# RfM_v4_KOVAN.net
KiCad netlist of a schematic drawn in EAGLE
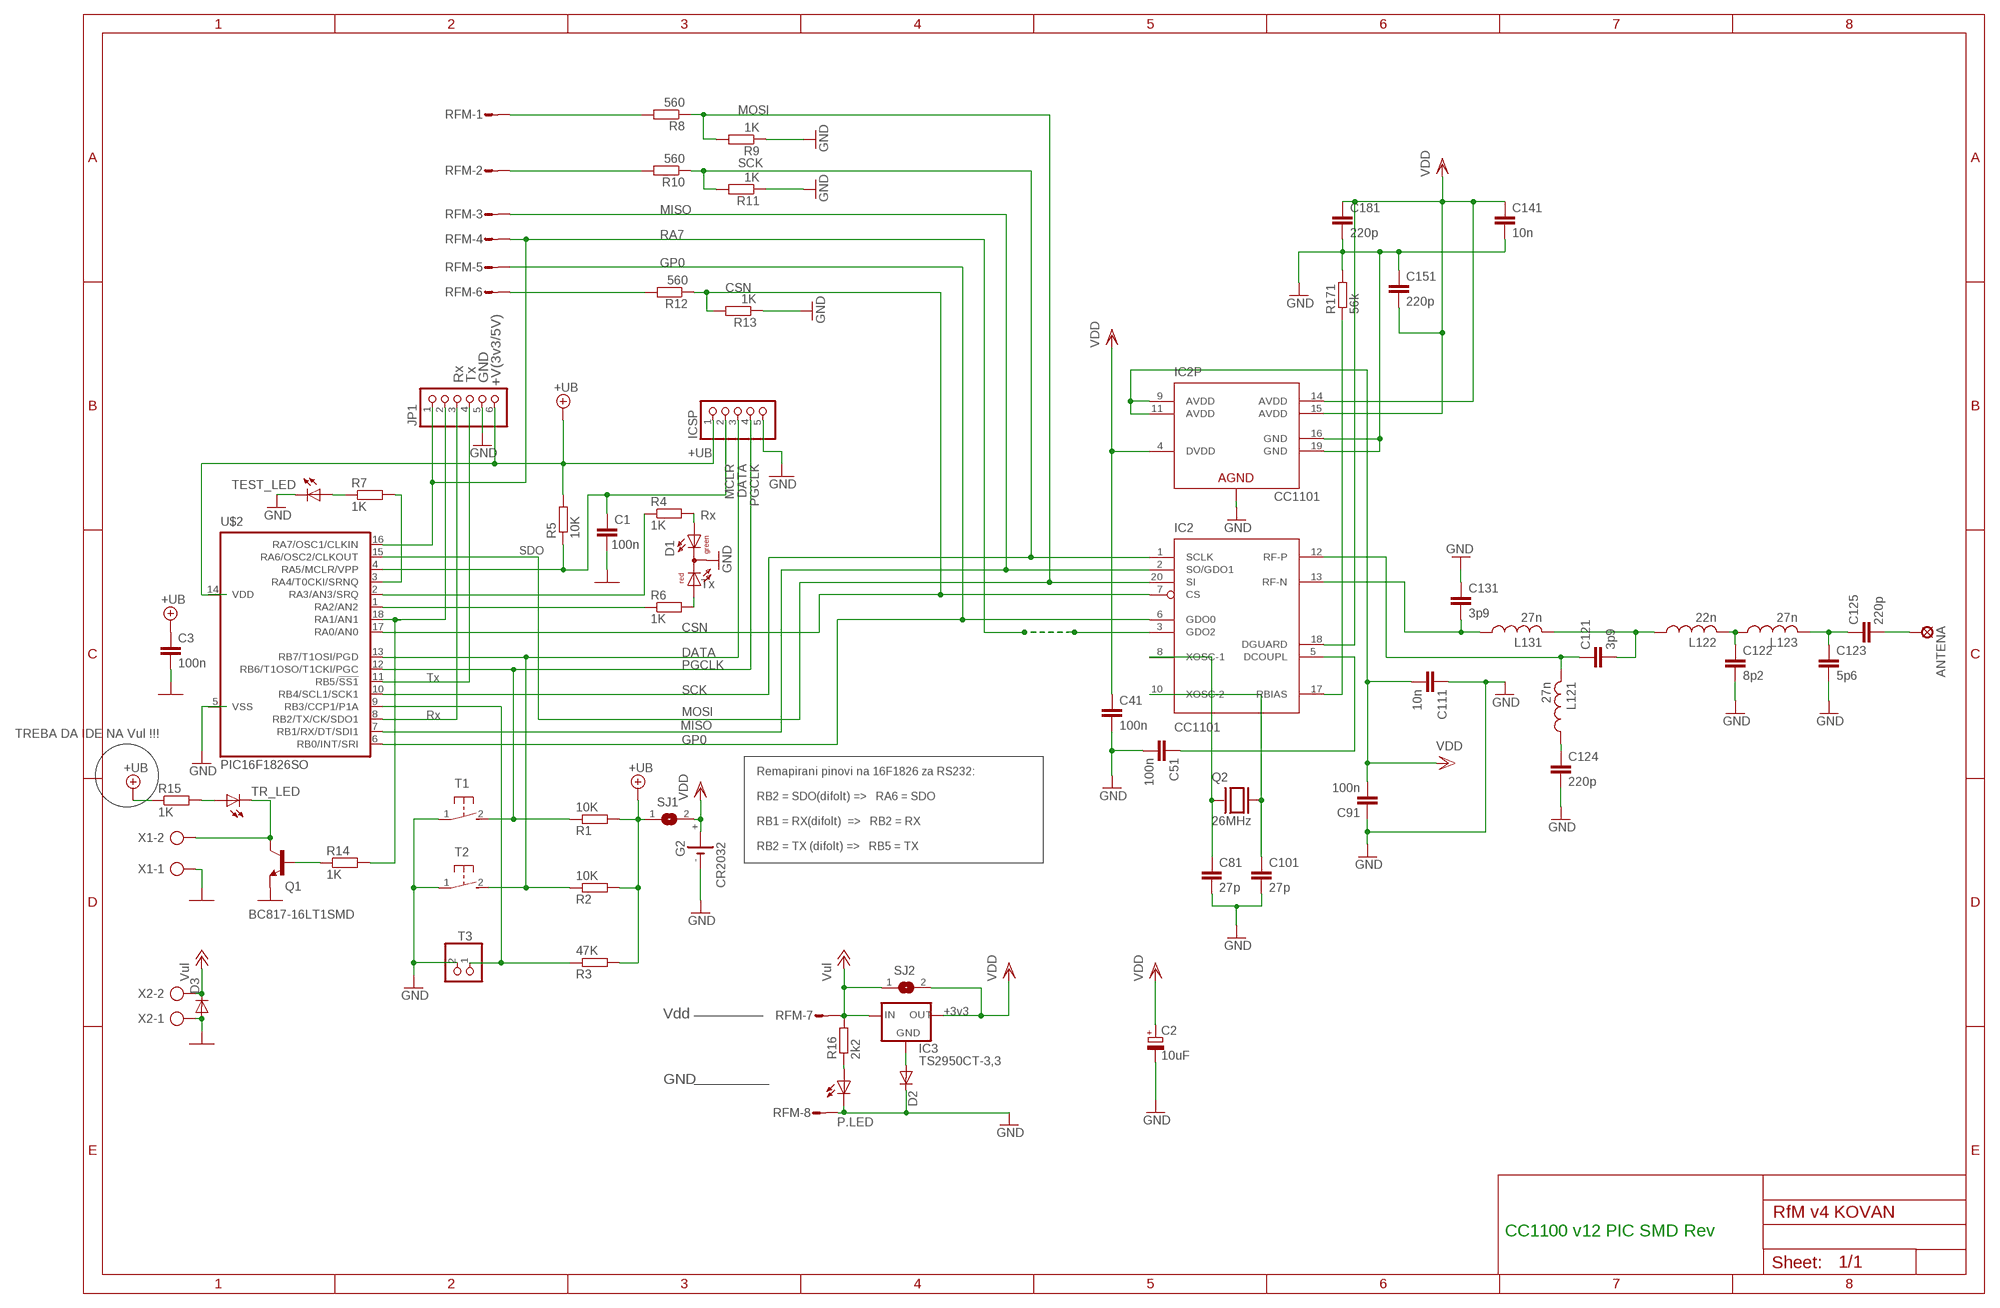
[diagram p0: schematic, sheet 1]

(export (version "E")
  (design (tool "Eeschema 10.0.6"))
  (components
    (comp (ref "ANTENA")
      (value "SE13")
      (footprint "eagle-import:SE13")
      (libsource (lib "eagle-import") (part "SE13"))
    )
    (comp (ref "C1")
      (value "100n")
      (footprint "eagle-import:C0805")
      (libsource (lib "eagle-import") (part "C-EUC0805"))
    )
    (comp (ref "C2")
      (value "10uF")
      (footprint "eagle-import:ALUCON")
      (libsource (lib "eagle-import") (part "CPOL-EUSMD"))
    )
    (comp (ref "C3")
      (value "100n")
      (footprint "eagle-import:C1206")
      (libsource (lib "eagle-import") (part "C-EUC1206"))
    )
    (comp (ref "C41")
      (value "100n")
      (footprint "eagle-import:C0402")
      (libsource (lib "eagle-import") (part "C-EUC0402"))
    )
    (comp (ref "C51")
      (value "100n")
      (footprint "eagle-import:C0402")
      (libsource (lib "eagle-import") (part "C-EUC0402"))
    )
    (comp (ref "C81")
      (value "27p")
      (footprint "eagle-import:C0402")
      (libsource (lib "eagle-import") (part "C-EUC0402"))
    )
    (comp (ref "C91")
      (value "100n")
      (footprint "eagle-import:C0402")
      (libsource (lib "eagle-import") (part "C-EUC0402"))
    )
    (comp (ref "C101")
      (value "27p")
      (footprint "eagle-import:C0402")
      (libsource (lib "eagle-import") (part "C-EUC0402"))
    )
    (comp (ref "C111")
      (value "10n")
      (footprint "eagle-import:C0402")
      (libsource (lib "eagle-import") (part "C-EUC0402"))
    )
    (comp (ref "C121")
      (value "3p9")
      (footprint "eagle-import:C0402")
      (libsource (lib "eagle-import") (part "C-EUC0402"))
    )
    (comp (ref "C122")
      (value "8p2")
      (footprint "eagle-import:C0402")
      (libsource (lib "eagle-import") (part "C-EUC0402"))
    )
    (comp (ref "C123")
      (value "5p6")
      (footprint "eagle-import:C0402")
      (libsource (lib "eagle-import") (part "C-EUC0402"))
    )
    (comp (ref "C124")
      (value "220p")
      (footprint "eagle-import:C0402")
      (libsource (lib "eagle-import") (part "C-EUC0402"))
    )
    (comp (ref "C125")
      (value "220p")
      (footprint "eagle-import:C0402")
      (libsource (lib "eagle-import") (part "C-EUC0402"))
    )
    (comp (ref "C131")
      (value "3p9")
      (footprint "eagle-import:C0402")
      (libsource (lib "eagle-import") (part "C-EUC0402"))
    )
    (comp (ref "C141")
      (value "10n")
      (footprint "eagle-import:C0402")
      (libsource (lib "eagle-import") (part "C-EUC0402"))
    )
    (comp (ref "C151")
      (value "220p")
      (footprint "eagle-import:C0402")
      (libsource (lib "eagle-import") (part "C-EUC0402"))
    )
    (comp (ref "C181")
      (value "220p")
      (footprint "eagle-import:C0402")
      (libsource (lib "eagle-import") (part "C-EUC0402"))
    )
    (comp (ref "D1")
      (value "DUOLED2X5.")
      (footprint "eagle-import:DUOLED2X5_")
      (libsource (lib "eagle-import") (part "DUOLED2X5."))
    )
    (comp (ref "D2")
      (value "1N4004SMD")
      (footprint "eagle-import:1N4007-SMD")
      (libsource (lib "eagle-import") (part "1N4004SMD"))
    )
    (comp (ref "D3")
      (value "1N4004SMD")
      (footprint "eagle-import:1N4007-SMD")
      (libsource (lib "eagle-import") (part "1N4004SMD"))
    )
    (comp (ref "G2")
      (value "CR2032")
      (footprint "eagle-import:CR2032--")
      (libsource (lib "eagle-import") (part "CR2032H,"))
    )
    (comp (ref "IC2")
      (value "CC1101")
      (footprint "eagle-import:QLP-20")
      (libsource (lib "eagle-import") (part "CC1100"))
    )
    (comp (ref "IC3")
      (value "TS2950CT-3,3")
      (footprint "eagle-import:78LXX")
      (libsource (lib "eagle-import") (part "78LXX"))
    )
    (comp (ref "ICSP")
      (value "PINHD-1X5.")
      (footprint "eagle-import:1X05.")
      (libsource (lib "eagle-import") (part "PINHD-1X5."))
    )
    (comp (ref "JP1")
      (value "PINHD-1X6.")
      (footprint "eagle-import:1X06.")
      (libsource (lib "eagle-import") (part "PINHD-1X6."))
    )
    (comp (ref "L121")
      (value "27n")
      (footprint "eagle-import:C0402")
      (libsource (lib "eagle-import") (part "L-USL0402"))
    )
    (comp (ref "L122")
      (value "22n")
      (footprint "eagle-import:C0402")
      (libsource (lib "eagle-import") (part "L-USL0402"))
    )
    (comp (ref "L123")
      (value "27n")
      (footprint "eagle-import:C0402")
      (libsource (lib "eagle-import") (part "L-USL0402"))
    )
    (comp (ref "L131")
      (value "27n")
      (footprint "eagle-import:C0402")
      (libsource (lib "eagle-import") (part "L-USL0402"))
    )
    (comp (ref "P.LED")
      (value "zelena")
      (footprint "eagle-import:CHIPLED_0805")
      (libsource (lib "eagle-import") (part "LEDCHIPLED_0805"))
    )
    (comp (ref "Q1")
      (value "BC817-16LT1SMD")
      (footprint "eagle-import:SOT23-BEC")
      (libsource (lib "eagle-import") (part "BC817SMD-16LT1"))
    )
    (comp (ref "Q2")
      (value "26MHz")
      (footprint "eagle-import:SMD")
      (libsource (lib "eagle-import") (part "XTALSMDMOJ"))
    )
    (comp (ref "R1")
      (value "10K")
      (footprint "eagle-import:R0805")
      (libsource (lib "eagle-import") (part "R-EU_R0805"))
    )
    (comp (ref "R2")
      (value "10K")
      (footprint "eagle-import:R0805")
      (libsource (lib "eagle-import") (part "R-EU_R0805"))
    )
    (comp (ref "R3")
      (value "47K")
      (footprint "eagle-import:R0603")
      (libsource (lib "eagle-import") (part "R-EU_R0603"))
    )
    (comp (ref "R4")
      (value "1K")
      (footprint "eagle-import:R0805")
      (libsource (lib "eagle-import") (part "R-EU_R0805"))
    )
    (comp (ref "R5")
      (value "10K")
      (footprint "eagle-import:R0603")
      (libsource (lib "eagle-import") (part "R-EU_R0603"))
    )
    (comp (ref "R6")
      (value "1K")
      (footprint "eagle-import:R0805")
      (libsource (lib "eagle-import") (part "R-EU_R0805"))
    )
    (comp (ref "R7")
      (value "1K")
      (footprint "eagle-import:R0603")
      (libsource (lib "eagle-import") (part "rcl-1_R-EU_R0603"))
    )
    (comp (ref "R8")
      (value "560")
      (footprint "eagle-import:R0603")
      (libsource (lib "eagle-import") (part "rcl_R-EU_R0603"))
    )
    (comp (ref "R9")
      (value "1K")
      (footprint "eagle-import:R0603")
      (libsource (lib "eagle-import") (part "rcl_R-EU_R0603"))
    )
    (comp (ref "R10")
      (value "560")
      (footprint "eagle-import:R0603")
      (libsource (lib "eagle-import") (part "rcl_R-EU_R0603"))
    )
    (comp (ref "R11")
      (value "1K")
      (footprint "eagle-import:R0603")
      (libsource (lib "eagle-import") (part "rcl_R-EU_R0603"))
    )
    (comp (ref "R12")
      (value "560")
      (footprint "eagle-import:R0603")
      (libsource (lib "eagle-import") (part "rcl_R-EU_R0603"))
    )
    (comp (ref "R13")
      (value "1K")
      (footprint "eagle-import:R0603")
      (libsource (lib "eagle-import") (part "rcl_R-EU_R0603"))
    )
    (comp (ref "R14")
      (value "1K")
      (footprint "eagle-import:R1206")
      (libsource (lib "eagle-import") (part "rcl-1_R-EU_R1206"))
    )
    (comp (ref "R15")
      (value "1K")
      (footprint "eagle-import:R0603")
      (libsource (lib "eagle-import") (part "rcl-1_R-EU_R0603"))
    )
    (comp (ref "R16")
      (value "2k2")
      (footprint "eagle-import:R0805")
      (libsource (lib "eagle-import") (part "rcl-1_R-EU_R0805"))
    )
    (comp (ref "R171")
      (value "56k")
      (footprint "eagle-import:R0402")
      (libsource (lib "eagle-import") (part "rcl_R-EU_R0402"))
    )
    (comp (ref "RFM")
      (value "MICROMATCH-8'")
      (footprint "eagle-import:MICROMATCH-8..")
      (libsource (lib "eagle-import") (part "MICROMATCH-8'"))
    )
    (comp (ref "SJ1") (value "SJ") (footprint "eagle-import:SJ") (libsource (lib "eagle-import") (part "SJ")))
    (comp (ref "SJ2") (value "SJ") (footprint "eagle-import:SJ") (libsource (lib "eagle-import") (part "SJ")))
    (comp (ref "T1")
      (value "10-XX-1'")
      (footprint "eagle-import:3BF-10XX-1.")
      (libsource (lib "eagle-import") (part "10-XX-1'"))
    )
    (comp (ref "T2")
      (value "10-XX-1'")
      (footprint "eagle-import:3BF-10XX-1.")
      (libsource (lib "eagle-import") (part "10-XX-1'"))
    )
    (comp (ref "T3")
      (value "PINHD-1X2.")
      (footprint "eagle-import:1X02.")
      (libsource (lib "eagle-import") (part "PINHD-1X2."))
    )
    (comp (ref "TEST_LED")
      (value "TEST_LED")
      (footprint "eagle-import:CHIPLED_0805")
      (libsource (lib "eagle-import") (part "LEDCHIPLED_0805"))
    )
    (comp (ref "TR_LED")
      (value "TEST_LED")
      (footprint "eagle-import:CHIPLED_0805")
      (libsource (lib "eagle-import") (part "LEDCHIPLED_0805"))
    )
    (comp (ref "U$2")
      (value "PIC16F1826SO")
      (footprint "eagle-import:SO-18W")
      (libsource (lib "eagle-import") (part "PIC16F1826SO"))
    )
    (comp (ref "X1")
      (value "AK300/2")
      (footprint "eagle-import:AK300_2")
      (libsource (lib "eagle-import") (part "AK300/2"))
    )
    (comp (ref "X2")
      (value "AK300/2")
      (footprint "eagle-import:AK300_2")
      (libsource (lib "eagle-import") (part "AK300/2"))
    )
  )
  (nets
    (net (code "1") (name "+UB") (class "Default")
      (node (ref "C3") (pin "2") (pinfunction "2_2") (pintype "passive"))
      (node (ref "ICSP") (pin "1") (pinfunction "1_1") (pintype "passive"))
      (node (ref "JP1") (pin "6") (pinfunction "6_6") (pintype "passive"))
      (node (ref "R1") (pin "2") (pinfunction "2_2") (pintype "passive"))
      (node (ref "R15") (pin "1") (pinfunction "1_1") (pintype "passive"))
      (node (ref "R2") (pin "2") (pinfunction "2_2") (pintype "passive"))
      (node (ref "R3") (pin "2") (pinfunction "2_2") (pintype "passive"))
      (node (ref "R5") (pin "2") (pinfunction "2_2") (pintype "passive"))
      (node (ref "SJ1") (pin "1") (pinfunction "1_1") (pintype "passive"))
      (node (ref "U$2") (pin "14") (pinfunction "VDD_14") (pintype "power_in"))
    )
    (net (code "2") (name "/CSN") (class "Default")
      (node (ref "IC2") (pin "7") (pinfunction "CS_7") (pintype "input"))
      (node (ref "R12") (pin "1") (pinfunction "1_1") (pintype "passive"))
      (node (ref "R13") (pin "2") (pinfunction "2_2") (pintype "passive"))
      (node (ref "U$2") (pin "17") (pinfunction "RA0/AN0_17") (pintype "bidirectional"))
    )
    (net (code "3") (name "/DATA") (class "Default")
      (node (ref "ICSP") (pin "3") (pinfunction "3_3") (pintype "passive"))
      (node (ref "R2") (pin "1") (pinfunction "1_1") (pintype "passive"))
      (node (ref "T2") (pin "2") (pinfunction "S_2") (pintype "passive"))
      (node (ref "U$2") (pin "13") (pinfunction "RB7/T1OSI/PGD_13") (pintype "bidirectional"))
    )
    (net (code "4") (name "/GP0") (class "Default")
      (node (ref "IC2") (pin "6") (pinfunction "GDO0_6") (pintype "output"))
      (node (ref "RFM") (pin "5") (pinfunction "S_5") (pintype "passive"))
      (node (ref "U$2") (pin "6") (pinfunction "RB0/INT/SRI_6") (pintype "bidirectional"))
    )
    (net (code "5") (name "/MCLR") (class "Default")
      (node (ref "C1") (pin "2") (pinfunction "2_2") (pintype "passive"))
      (node (ref "ICSP") (pin "2") (pinfunction "2_2") (pintype "passive"))
      (node (ref "R5") (pin "1") (pinfunction "1_1") (pintype "passive"))
      (node (ref "U$2") (pin "4") (pinfunction "RA5/MCLR/VPP_4") (pintype "bidirectional"))
    )
    (net (code "6") (name "/MISO") (class "Default")
      (node (ref "IC2") (pin "2") (pinfunction "SO/GDO1_2") (pintype "output"))
      (node (ref "RFM") (pin "3") (pinfunction "S_3") (pintype "passive"))
      (node (ref "U$2") (pin "7") (pinfunction "RB1/RX/DT/SDI1_7") (pintype "bidirectional"))
    )
    (net (code "7") (name "/MOSI") (class "Default")
      (node (ref "IC2") (pin "20") (pinfunction "SI_20") (pintype "input"))
      (node (ref "R8") (pin "1") (pinfunction "1_1") (pintype "passive"))
      (node (ref "R9") (pin "2") (pinfunction "2_2") (pintype "passive"))
      (node (ref "U$2") (pin "15") (pinfunction "RA6/OSC2/CLKOUT_15") (pintype "bidirectional"))
    )
    (net (code "8") (name "/PGCLK") (class "Default")
      (node (ref "ICSP") (pin "4") (pinfunction "4_4") (pintype "passive"))
      (node (ref "R1") (pin "1") (pinfunction "1_1") (pintype "passive"))
      (node (ref "T1") (pin "2") (pinfunction "S_2") (pintype "passive"))
      (node (ref "U$2") (pin "12") (pinfunction "RB6/T1OSO/T1CKI/PGC_12") (pintype "bidirectional"))
    )
    (net (code "9") (name "/RA7") (class "Default")
      (node (ref "JP1") (pin "1") (pinfunction "1_1") (pintype "passive"))
      (node (ref "RFM") (pin "4") (pinfunction "S_4") (pintype "passive"))
      (node (ref "U$2") (pin "16") (pinfunction "RA7/OSC1/CLKIN_16") (pintype "bidirectional"))
    )
    (net (code "10") (name "/SCK") (class "Default")
      (node (ref "IC2") (pin "1") (pinfunction "SCLK_1") (pintype "input"))
      (node (ref "R10") (pin "1") (pinfunction "1_1") (pintype "passive"))
      (node (ref "R11") (pin "2") (pinfunction "2_2") (pintype "passive"))
      (node (ref "U$2") (pin "10") (pinfunction "RB4/SCL1/SCK1_10") (pintype "bidirectional"))
    )
    (net (code "11") (name "GND") (class "Default")
      (node (ref "C1") (pin "1") (pinfunction "1_1") (pintype "passive"))
      (node (ref "C101") (pin "1") (pinfunction "1_1") (pintype "passive"))
      (node (ref "C111") (pin "2") (pinfunction "2_2") (pintype "passive"))
      (node (ref "C122") (pin "1") (pinfunction "1_1") (pintype "passive"))
      (node (ref "C123") (pin "1") (pinfunction "1_1") (pintype "passive"))
      (node (ref "C124") (pin "1") (pinfunction "1_1") (pintype "passive"))
      (node (ref "C131") (pin "2") (pinfunction "2_2") (pintype "passive"))
      (node (ref "C141") (pin "1") (pinfunction "1_1") (pintype "passive"))
      (node (ref "C151") (pin "2") (pinfunction "2_2") (pintype "passive"))
      (node (ref "C181") (pin "1") (pinfunction "1_1") (pintype "passive"))
      (node (ref "C2") (pin "P$1") (pinfunction "-_P$1") (pintype "passive"))
      (node (ref "C3") (pin "1") (pinfunction "1_1") (pintype "passive"))
      (node (ref "C41") (pin "1") (pinfunction "1_1") (pintype "passive"))
      (node (ref "C51") (pin "1") (pinfunction "1_1") (pintype "passive"))
      (node (ref "C81") (pin "1") (pinfunction "1_1") (pintype "passive"))
      (node (ref "C91") (pin "2") (pinfunction "2_2") (pintype "passive"))
      (node (ref "D1") (pin "K") (pinfunction "C_K") (pintype "passive"))
      (node (ref "D2") (pin "C") (pinfunction "C_C") (pintype "passive"))
      (node (ref "D3") (pin "A") (pinfunction "A_A") (pintype "passive"))
      (node (ref "G2") (pin "-") (pinfunction "-_-") (pintype "passive"))
      (node (ref "IC2") (pin "16") (pinfunction "GND_16") (pintype "power_in"))
      (node (ref "IC2") (pin "19") (pinfunction "GND_19") (pintype "power_in"))
      (node (ref "IC2") (pin "21") (pinfunction "AGND_21") (pintype "power_in"))
      (node (ref "ICSP") (pin "5") (pinfunction "5_5") (pintype "passive"))
      (node (ref "JP1") (pin "5") (pinfunction "5_5") (pintype "passive"))
      (node (ref "Q1") (pin "E") (pinfunction "E_E") (pintype "passive"))
      (node (ref "R11") (pin "1") (pinfunction "1_1") (pintype "passive"))
      (node (ref "R13") (pin "1") (pinfunction "1_1") (pintype "passive"))
      (node (ref "R171") (pin "2") (pinfunction "2_2") (pintype "passive"))
      (node (ref "R9") (pin "1") (pinfunction "1_1") (pintype "passive"))
      (node (ref "RFM") (pin "8") (pinfunction "S_8") (pintype "passive"))
      (node (ref "T1") (pin "1") (pinfunction "P_1") (pintype "passive"))
      (node (ref "T2") (pin "1") (pinfunction "P_1") (pintype "passive"))
      (node (ref "T3") (pin "2") (pinfunction "2_2") (pintype "passive"))
      (node (ref "TEST_LED") (pin "C") (pinfunction "C_C") (pintype "passive"))
      (node (ref "U$2") (pin "5") (pinfunction "VSS_5") (pintype "power_in"))
      (node (ref "X1") (pin "1") (pinfunction "KL_1") (pintype "passive"))
      (node (ref "X2") (pin "1") (pinfunction "KL_1") (pintype "passive"))
    )
    (net (code "12") (name "Net-(ANTENA-PadMP)") (class "Default")
      (node (ref "ANTENA") (pin "MP") (pinfunction "MP_MP") (pintype "passive"))
      (node (ref "C125") (pin "1") (pinfunction "1_1") (pintype "passive"))
    )
    (net (code "13") (name "Net-(C121-Pad1)") (class "Default")
      (node (ref "C121") (pin "1") (pinfunction "1_1") (pintype "passive"))
      (node (ref "L122") (pin "2") (pinfunction "2_2") (pintype "passive"))
      (node (ref "L131") (pin "1") (pinfunction "1_1") (pintype "passive"))
    )
    (net (code "14") (name "Net-(C122-Pad2)") (class "Default")
      (node (ref "C122") (pin "2") (pinfunction "2_2") (pintype "passive"))
      (node (ref "L122") (pin "1") (pinfunction "1_1") (pintype "passive"))
      (node (ref "L123") (pin "2") (pinfunction "2_2") (pintype "passive"))
    )
    (net (code "15") (name "Net-(C123-Pad2)") (class "Default")
      (node (ref "C123") (pin "2") (pinfunction "2_2") (pintype "passive"))
      (node (ref "C125") (pin "2") (pinfunction "2_2") (pintype "passive"))
      (node (ref "L123") (pin "1") (pinfunction "1_1") (pintype "passive"))
    )
    (net (code "16") (name "Net-(C124-Pad2)") (class "Default")
      (node (ref "C124") (pin "2") (pinfunction "2_2") (pintype "passive"))
      (node (ref "L121") (pin "2") (pinfunction "2_2") (pintype "passive"))
    )
    (net (code "17") (name "Net-(D1-PadAG)") (class "Default")
      (node (ref "D1") (pin "AG") (pinfunction "AG_AG") (pintype "passive"))
      (node (ref "R4") (pin "2") (pinfunction "2_2") (pintype "passive"))
    )
    (net (code "18") (name "Net-(D1-PadAR)") (class "Default")
      (node (ref "D1") (pin "AR") (pinfunction "AR_AR") (pintype "passive"))
      (node (ref "R6") (pin "2") (pinfunction "2_2") (pintype "passive"))
    )
    (net (code "19") (name "Net-(D2-PadA)") (class "Default")
      (node (ref "D2") (pin "A") (pinfunction "A_A") (pintype "passive"))
      (node (ref "IC3") (pin "GND") (pinfunction "GND_GND") (pintype "input"))
    )
    (net (code "20") (name "Net-(IC2A-DCOUPL)") (class "Default")
      (node (ref "C51") (pin "2") (pinfunction "2_2") (pintype "passive"))
      (node (ref "IC2") (pin "5") (pinfunction "DCOUPL_5") (pintype "power_in"))
    )
    (net (code "21") (name "Net-(IC2A-RBIAS)") (class "Default")
      (node (ref "IC2") (pin "17") (pinfunction "RBIAS_17") (pintype "bidirectional"))
      (node (ref "R171") (pin "1") (pinfunction "1_1") (pintype "passive"))
    )
    (net (code "22") (name "Net-(IC2A-RF-N)") (class "Default")
      (node (ref "C131") (pin "1") (pinfunction "1_1") (pintype "passive"))
      (node (ref "IC2") (pin "13") (pinfunction "RF-N_13") (pintype "bidirectional"))
      (node (ref "L131") (pin "2") (pinfunction "2_2") (pintype "passive"))
    )
    (net (code "23") (name "Net-(IC2A-RF-P)") (class "Default")
      (node (ref "C121") (pin "2") (pinfunction "2_2") (pintype "passive"))
      (node (ref "IC2") (pin "12") (pinfunction "RF-P_12") (pintype "bidirectional"))
      (node (ref "L121") (pin "1") (pinfunction "1_1") (pintype "passive"))
    )
    (net (code "24") (name "Net-(IC2A-XOSC-1)") (class "Default")
      (node (ref "C81") (pin "2") (pinfunction "2_2") (pintype "passive"))
      (node (ref "IC2") (pin "8") (pinfunction "XOSC-1_8") (pintype "input"))
      (node (ref "Q2") (pin "P$3") (pinfunction "1_P$3") (pintype "passive"))
    )
    (net (code "25") (name "Net-(IC2A-XOSC-2)") (class "Default")
      (node (ref "C101") (pin "2") (pinfunction "2_2") (pintype "passive"))
      (node (ref "IC2") (pin "10") (pinfunction "XOSC-2_10") (pintype "output"))
      (node (ref "Q2") (pin "P$5") (pinfunction "2_P$5") (pintype "passive"))
    )
    (net (code "26") (name "Net-(P.LED-PadA)") (class "Default")
      (node (ref "P.LED") (pin "A") (pinfunction "A_A") (pintype "passive"))
      (node (ref "R16") (pin "1") (pinfunction "1_1") (pintype "passive"))
    )
    (net (code "27") (name "Net-(Q1-PadB)") (class "Default")
      (node (ref "Q1") (pin "B") (pinfunction "B_B") (pintype "passive"))
      (node (ref "R14") (pin "1") (pinfunction "1_1") (pintype "passive"))
    )
    (net (code "28") (name "Net-(R7-Pad1)") (class "Default")
      (node (ref "R7") (pin "1") (pinfunction "1_1") (pintype "passive"))
      (node (ref "TEST_LED") (pin "A") (pinfunction "A_A") (pintype "passive"))
    )
    (net (code "29") (name "Net-(R15-Pad2)") (class "Default")
      (node (ref "R15") (pin "2") (pinfunction "2_2") (pintype "passive"))
      (node (ref "TR_LED") (pin "A") (pinfunction "A_A") (pintype "passive"))
    )
    (net (code "30") (name "Net-(RFMA-S)") (class "Default")
      (node (ref "R8") (pin "2") (pinfunction "2_2") (pintype "passive"))
      (node (ref "RFM") (pin "1") (pinfunction "S_1") (pintype "passive"))
    )
    (net (code "31") (name "Net-(RFMB-S)") (class "Default")
      (node (ref "R10") (pin "2") (pinfunction "2_2") (pintype "passive"))
      (node (ref "RFM") (pin "2") (pinfunction "S_2") (pintype "passive"))
    )
    (net (code "32") (name "Net-(RFMF-S)") (class "Default")
      (node (ref "R12") (pin "2") (pinfunction "2_2") (pintype "passive"))
      (node (ref "RFM") (pin "6") (pinfunction "S_6") (pintype "passive"))
    )
    (net (code "33") (name "Net-(U$2-RA1{slash}AN1)") (class "Default")
      (node (ref "JP1") (pin "2") (pinfunction "2_2") (pintype "passive"))
      (node (ref "R14") (pin "2") (pinfunction "2_2") (pintype "passive"))
      (node (ref "U$2") (pin "18") (pinfunction "RA1/AN1_18") (pintype "bidirectional"))
    )
    (net (code "34") (name "Net-(U$2-RA2{slash}AN2)") (class "Default")
      (node (ref "R6") (pin "1") (pinfunction "1_1") (pintype "passive"))
      (node (ref "U$2") (pin "1") (pinfunction "RA2/AN2_1") (pintype "bidirectional"))
    )
    (net (code "35") (name "Net-(U$2-RA3{slash}AN3{slash}SRQ)") (class "Default")
      (node (ref "R4") (pin "1") (pinfunction "1_1") (pintype "passive"))
      (node (ref "U$2") (pin "2") (pinfunction "RA3/AN3/SRQ_2") (pintype "bidirectional"))
    )
    (net (code "36") (name "Net-(U$2-RA4{slash}T0CKI{slash}SRNQ)") (class "Default")
      (node (ref "R7") (pin "2") (pinfunction "2_2") (pintype "passive"))
      (node (ref "U$2") (pin "3") (pinfunction "RA4/T0CKI/SRNQ_3") (pintype "bidirectional"))
    )
    (net (code "37") (name "Net-(U$2-RB2{slash}TX{slash}CK{slash}SDO1)") (class "Default")
      (node (ref "JP1") (pin "3") (pinfunction "3_3") (pintype "passive"))
      (node (ref "U$2") (pin "8") (pinfunction "RB2/TX/CK/SDO1_8") (pintype "bidirectional"))
    )
    (net (code "38") (name "Net-(U$2-RB3{slash}CCP1{slash}P1A)") (class "Default")
      (node (ref "R3") (pin "1") (pinfunction "1_1") (pintype "passive"))
      (node (ref "T3") (pin "1") (pinfunction "1_1") (pintype "passive"))
      (node (ref "U$2") (pin "9") (pinfunction "RB3/CCP1/P1A_9") (pintype "bidirectional"))
    )
    (net (code "39") (name "Net-(U$2-RB5{slash}~{SS1})") (class "Default")
      (node (ref "JP1") (pin "4") (pinfunction "4_4") (pintype "passive"))
      (node (ref "U$2") (pin "11") (pinfunction "RB5/~{SS1}_11") (pintype "bidirectional"))
    )
    (net (code "40") (name "Net-(X1B-KL)") (class "Default")
      (node (ref "Q1") (pin "C") (pinfunction "C_C") (pintype "passive"))
      (node (ref "TR_LED") (pin "C") (pinfunction "C_C") (pintype "passive"))
      (node (ref "X1") (pin "2") (pinfunction "KL_2") (pintype "passive"))
    )
    (net (code "41") (name "VDD") (class "Default")
      (node (ref "C111") (pin "1") (pinfunction "1_1") (pintype "passive"))
      (node (ref "C141") (pin "2") (pinfunction "2_2") (pintype "passive"))
      (node (ref "C151") (pin "1") (pinfunction "1_1") (pintype "passive"))
      (node (ref "C181") (pin "2") (pinfunction "2_2") (pintype "passive"))
      (node (ref "C2") (pin "P$4") (pinfunction "+_P$4") (pintype "passive"))
      (node (ref "C41") (pin "2") (pinfunction "2_2") (pintype "passive"))
      (node (ref "C91") (pin "1") (pinfunction "1_1") (pintype "passive"))
      (node (ref "G2") (pin "+") (pinfunction "+_+") (pintype "passive"))
      (node (ref "G2") (pin "+@1") (pinfunction "+_+@1") (pintype "passive"))
      (node (ref "IC2") (pin "11") (pinfunction "AVDD_11") (pintype "power_in"))
      (node (ref "IC2") (pin "14") (pinfunction "AVDD_14") (pintype "power_in"))
      (node (ref "IC2") (pin "15") (pinfunction "AVDD_15") (pintype "power_in"))
      (node (ref "IC2") (pin "18") (pinfunction "DGUARD_18") (pintype "power_in"))
      (node (ref "IC2") (pin "4") (pinfunction "DVDD_4") (pintype "power_in"))
      (node (ref "IC2") (pin "9") (pinfunction "AVDD_9") (pintype "power_in"))
      (node (ref "IC3") (pin "OUT") (pinfunction "OUT_OUT") (pintype "passive"))
      (node (ref "SJ1") (pin "2") (pinfunction "2_2") (pintype "passive"))
      (node (ref "SJ2") (pin "2") (pinfunction "2_2") (pintype "passive"))
    )
    (net (code "42") (name "Vul") (class "Default")
      (node (ref "D3") (pin "C") (pinfunction "C_C") (pintype "passive"))
      (node (ref "IC3") (pin "IN") (pinfunction "IN_IN") (pintype "input"))
      (node (ref "R16") (pin "2") (pinfunction "2_2") (pintype "passive"))
      (node (ref "RFM") (pin "7") (pinfunction "S_7") (pintype "passive"))
      (node (ref "SJ2") (pin "1") (pinfunction "1_1") (pintype "passive"))
      (node (ref "X2") (pin "2") (pinfunction "KL_2") (pintype "passive"))
    )
    (net (code "43") (name "unconnected-(IC2A-GDO2-Pad3)") (class "Default")
      (node (ref "IC2") (pin "3") (pinfunction "GDO2_3") (pintype "output"))
    )
    (net (code "44") (name "unconnected-(P.LED-PadC)") (class "Default")
      (node (ref "P.LED") (pin "C") (pinfunction "C_C") (pintype "passive"))
    )
  )
)
